# Lodi_Mult_PCB_v002.net
KiCad netlist of a schematic drawn in EAGLE
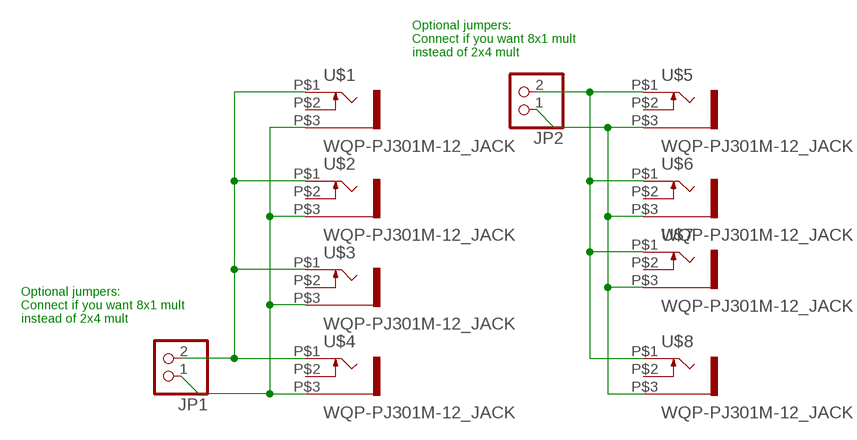
[diagram p0: schematic, sheet 1]

(export (version "E")
  (design (tool "Eeschema 10.0.6"))
  (components
    (comp (ref "JP1")
      (value "PINHD-1X2")
      (footprint "eagle-import:1X02")
      (libsource (lib "eagle-import") (part "PINHD-1X2"))
    )
    (comp (ref "JP2")
      (value "PINHD-1X2")
      (footprint "eagle-import:1X02")
      (libsource (lib "eagle-import") (part "PINHD-1X2"))
    )
    (comp (ref "U$1")
      (value "WQP-PJ301M-12_JACK")
      (footprint "eagle-import:WQP-PJ301M-12_JACK")
      (libsource (lib "eagle-import") (part "WQP-PJ301M-12_JACK"))
    )
    (comp (ref "U$2")
      (value "WQP-PJ301M-12_JACK")
      (footprint "eagle-import:WQP-PJ301M-12_JACK")
      (libsource (lib "eagle-import") (part "WQP-PJ301M-12_JACK"))
    )
    (comp (ref "U$3")
      (value "WQP-PJ301M-12_JACK")
      (footprint "eagle-import:WQP-PJ301M-12_JACK")
      (libsource (lib "eagle-import") (part "WQP-PJ301M-12_JACK"))
    )
    (comp (ref "U$4")
      (value "WQP-PJ301M-12_JACK")
      (footprint "eagle-import:WQP-PJ301M-12_JACK")
      (libsource (lib "eagle-import") (part "WQP-PJ301M-12_JACK"))
    )
    (comp (ref "U$5")
      (value "WQP-PJ301M-12_JACK")
      (footprint "eagle-import:WQP-PJ301M-12_JACK")
      (libsource (lib "eagle-import") (part "WQP-PJ301M-12_JACK"))
    )
    (comp (ref "U$6")
      (value "WQP-PJ301M-12_JACK")
      (footprint "eagle-import:WQP-PJ301M-12_JACK")
      (libsource (lib "eagle-import") (part "WQP-PJ301M-12_JACK"))
    )
    (comp (ref "U$7")
      (value "WQP-PJ301M-12_JACK")
      (footprint "eagle-import:WQP-PJ301M-12_JACK")
      (libsource (lib "eagle-import") (part "WQP-PJ301M-12_JACK"))
    )
    (comp (ref "U$8")
      (value "WQP-PJ301M-12_JACK")
      (footprint "eagle-import:WQP-PJ301M-12_JACK")
      (libsource (lib "eagle-import") (part "WQP-PJ301M-12_JACK"))
    )
  )
  (nets
    (net (code "1") (name "Net-(U$1-1)") (class "Default")
      (node (ref "JP1") (pin "1") (pinfunction "1_1") (pintype "passive"))
      (node (ref "U$1") (pin "P$3") (pinfunction "1_P$3") (pintype "passive"))
      (node (ref "U$2") (pin "P$3") (pinfunction "1_P$3") (pintype "passive"))
      (node (ref "U$3") (pin "P$3") (pinfunction "1_P$3") (pintype "passive"))
      (node (ref "U$4") (pin "P$3") (pinfunction "1_P$3") (pintype "passive"))
    )
    (net (code "2") (name "Net-(U$1-2)") (class "Default")
      (node (ref "JP1") (pin "2") (pinfunction "2_2") (pintype "passive"))
      (node (ref "U$1") (pin "P$1") (pinfunction "2_P$1") (pintype "passive"))
      (node (ref "U$2") (pin "P$1") (pinfunction "2_P$1") (pintype "passive"))
      (node (ref "U$3") (pin "P$1") (pinfunction "2_P$1") (pintype "passive"))
      (node (ref "U$4") (pin "P$1") (pinfunction "2_P$1") (pintype "passive"))
    )
    (net (code "3") (name "Net-(U$5-1)") (class "Default")
      (node (ref "JP2") (pin "1") (pinfunction "1_1") (pintype "passive"))
      (node (ref "U$5") (pin "P$3") (pinfunction "1_P$3") (pintype "passive"))
      (node (ref "U$6") (pin "P$3") (pinfunction "1_P$3") (pintype "passive"))
      (node (ref "U$7") (pin "P$3") (pinfunction "1_P$3") (pintype "passive"))
      (node (ref "U$8") (pin "P$3") (pinfunction "1_P$3") (pintype "passive"))
    )
    (net (code "4") (name "Net-(U$5-2)") (class "Default")
      (node (ref "JP2") (pin "2") (pinfunction "2_2") (pintype "passive"))
      (node (ref "U$5") (pin "P$1") (pinfunction "2_P$1") (pintype "passive"))
      (node (ref "U$6") (pin "P$1") (pinfunction "2_P$1") (pintype "passive"))
      (node (ref "U$7") (pin "P$1") (pinfunction "2_P$1") (pintype "passive"))
      (node (ref "U$8") (pin "P$1") (pinfunction "2_P$1") (pintype "passive"))
    )
    (net (code "5") (name "unconnected-(U$1-3-PadP$2)") (class "Default")
      (node (ref "U$1") (pin "P$2") (pinfunction "3_P$2") (pintype "passive"))
    )
    (net (code "6") (name "unconnected-(U$2-3-PadP$2)") (class "Default")
      (node (ref "U$2") (pin "P$2") (pinfunction "3_P$2") (pintype "passive"))
    )
    (net (code "7") (name "unconnected-(U$3-3-PadP$2)") (class "Default")
      (node (ref "U$3") (pin "P$2") (pinfunction "3_P$2") (pintype "passive"))
    )
    (net (code "8") (name "unconnected-(U$4-3-PadP$2)") (class "Default")
      (node (ref "U$4") (pin "P$2") (pinfunction "3_P$2") (pintype "passive"))
    )
    (net (code "9") (name "unconnected-(U$5-3-PadP$2)") (class "Default")
      (node (ref "U$5") (pin "P$2") (pinfunction "3_P$2") (pintype "passive"))
    )
    (net (code "10") (name "unconnected-(U$6-3-PadP$2)") (class "Default")
      (node (ref "U$6") (pin "P$2") (pinfunction "3_P$2") (pintype "passive"))
    )
    (net (code "11") (name "unconnected-(U$7-3-PadP$2)") (class "Default")
      (node (ref "U$7") (pin "P$2") (pinfunction "3_P$2") (pintype "passive"))
    )
    (net (code "12") (name "unconnected-(U$8-3-PadP$2)") (class "Default")
      (node (ref "U$8") (pin "P$2") (pinfunction "3_P$2") (pintype "passive"))
    )
  )
)
